# AltairLCD.net
KiCad netlist of a schematic drawn in EasyEDA
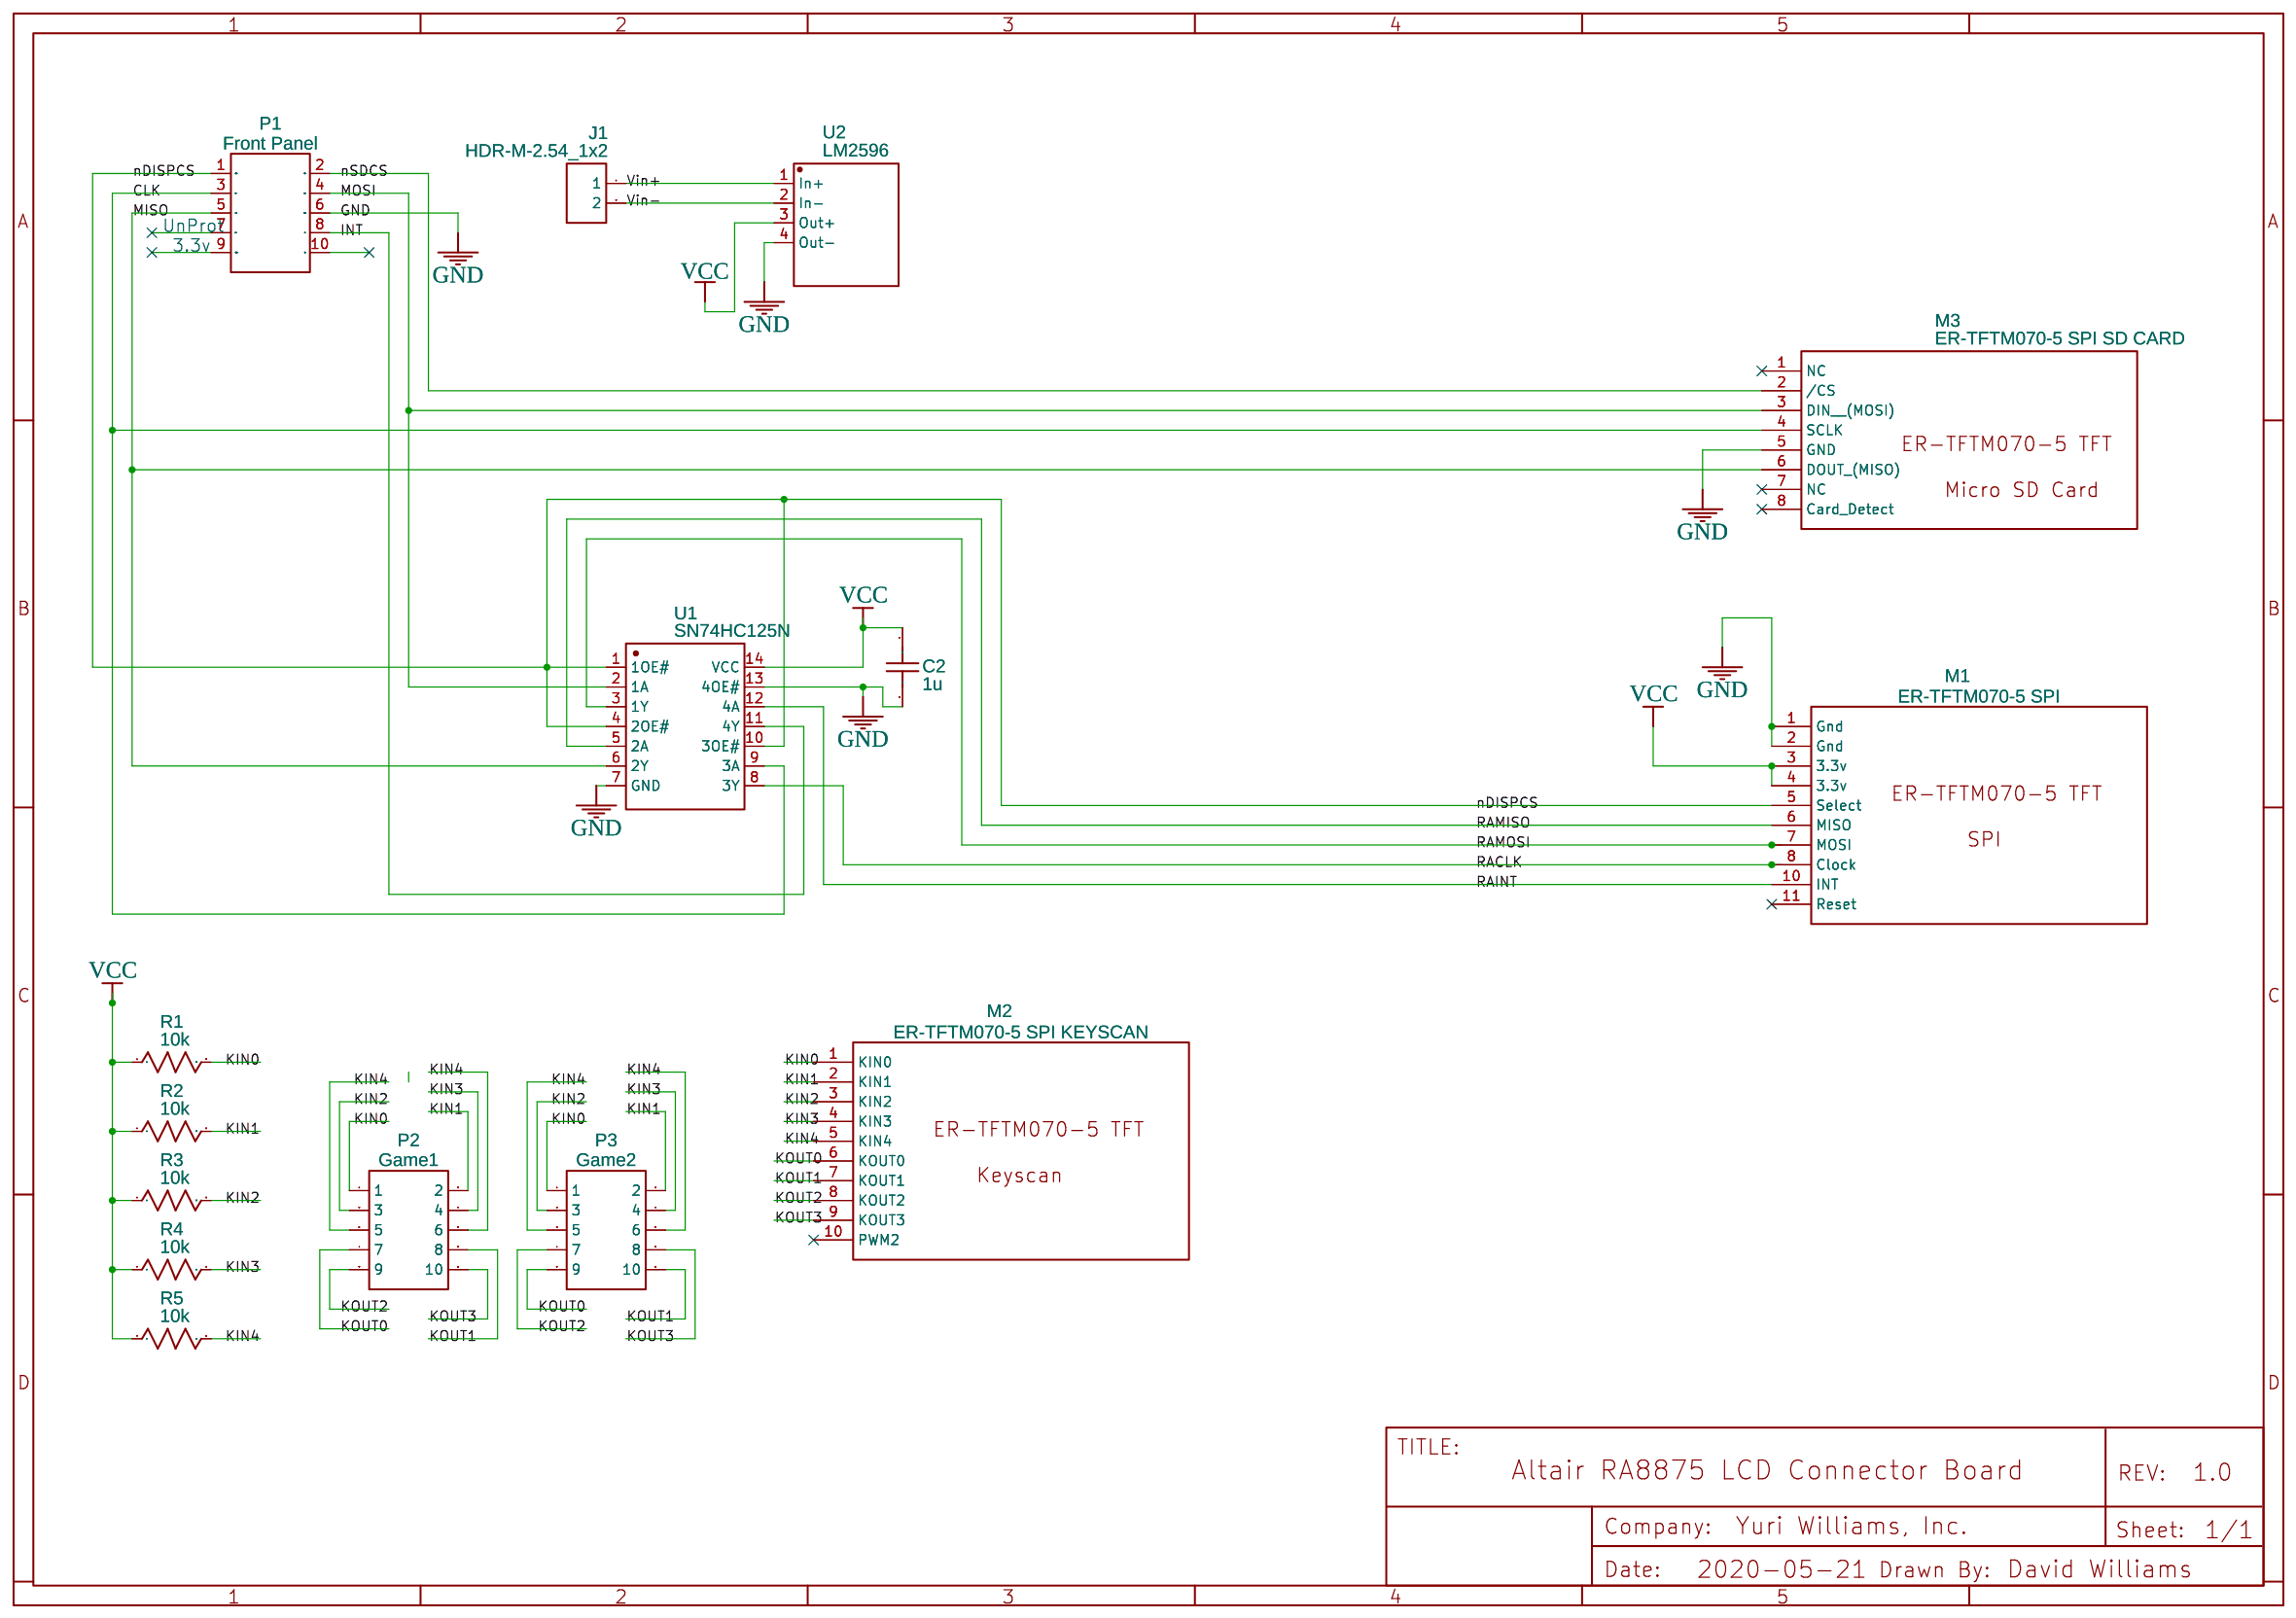
[diagram p0: schematic sheet]

(export (version "E")
  (design (tool "Eeschema 10.0.6"))
  (components
    (comp (ref "C2") (value "1u") (libsource (lib "") (part "C_RAD-0.1_US")))
    (comp (ref "J1")
      (value "HDR-M-2.54_1x2")
      (fields (field (name "BOM_Supplier Part") "C124375"))
      (libsource (lib "") (part "HDR-M-2.54_1x2"))
    )
    (comp (ref "M1")
      (value "ER-TFTM070-5 SPI")
      (fields
        (field (name "BOM_Manufacturer Part") "CD74HC125M")
        (field (name "BOM_Supplier Part") "ER-TFTM070-5")
      )
      (libsource (lib "") (part "ER-TFTM070-5 SPI"))
    )
    (comp (ref "M2")
      (value "ER-TFTM070-5 SPI KEYSCAN")
      (fields
        (field (name "BOM_Manufacturer Part") "CD74HC125M")
        (field (name "BOM_Supplier Part") "ER-TFTM070-5")
      )
      (libsource (lib "") (part "ER-TFTM070-5 SPI KEYSCAN"))
    )
    (comp (ref "M3")
      (value "ER-TFTM070-5 SPI SD CARD")
      (fields
        (field (name "BOM_Manufacturer Part") "CD74HC125M")
        (field (name "BOM_Supplier Part") "ER-TFTM070-5")
      )
      (libsource (lib "") (part "ER-TFTM070-5 SPI SD CARD"))
    )
    (comp (ref "P1")
      (value "Front Panel")
      (fields
        (field (name "BOM_Manufacturer Part") "IDC Box 2.54mm 2X5P")
        (field (name "BOM_Supplier Part") "C5665")
      )
      (libsource (lib "") (part "HDR-IDC-2.54-2X5P"))
    )
    (comp (ref "P2")
      (value "Game1")
      (fields
        (field (name "BOM_Manufacturer Part") "IDC Box 2.54mm 2X5P")
        (field (name "BOM_Supplier Part") "C5665")
      )
      (libsource (lib "") (part "HDR-IDC-2.54-2X5P_1"))
    )
    (comp (ref "P3")
      (value "Game2")
      (fields
        (field (name "BOM_Manufacturer Part") "IDC Box 2.54mm 2X5P")
        (field (name "BOM_Supplier Part") "C5665")
      )
      (libsource (lib "") (part "HDR-IDC-2.54-2X5P_1"))
    )
    (comp (ref "R1") (value "10k") (libsource (lib "") (part "R_AXIAL-0.3_US")))
    (comp (ref "R2") (value "10k") (libsource (lib "") (part "R_AXIAL-0.3_US")))
    (comp (ref "R3") (value "10k") (libsource (lib "") (part "R_AXIAL-0.3_US")))
    (comp (ref "R4") (value "10k") (libsource (lib "") (part "R_AXIAL-0.3_US")))
    (comp (ref "R5") (value "10k") (libsource (lib "") (part "R_AXIAL-0.3_US")))
    (comp (ref "U1")
      (value "SN74HC125N")
      (fields (field (name "BOM_Supplier Part") "C2890"))
      (libsource (lib "") (part "SN74HC125N"))
    )
    (comp (ref "U2") (value "LM2596") (libsource (lib "") (part "LM2596")))
  )
  (nets
    (net (code "1") (name "/CLK") (class "Default")
      (node (ref "M3") (pin "4") (pinfunction "SCLK_4") (pintype "unspecified"))
      (node (ref "P1") (pin "3") (pinfunction "CLK_3") (pintype "input"))
      (node (ref "U1") (pin "9") (pinfunction "3A_9") (pintype "unspecified"))
    )
    (net (code "2") (name "/INT") (class "Default")
      (node (ref "P1") (pin "8") (pinfunction "INT_8") (pintype "output"))
      (node (ref "U1") (pin "11") (pinfunction "4Y_11") (pintype "unspecified"))
    )
    (net (code "3") (name "/KIN0") (class "Default")
      (node (ref "M2") (pin "1") (pinfunction "KIN0_1") (pintype "unspecified"))
      (node (ref "P2") (pin "1") (pinfunction "1_1") (pintype "unspecified"))
      (node (ref "P3") (pin "1") (pinfunction "1_1") (pintype "unspecified"))
      (node (ref "R1") (pin "2") (pinfunction "2_2") (pintype "unspecified"))
    )
    (net (code "4") (name "/KIN1") (class "Default")
      (node (ref "M2") (pin "2") (pinfunction "KIN1_2") (pintype "unspecified"))
      (node (ref "P2") (pin "2") (pinfunction "2_2") (pintype "unspecified"))
      (node (ref "P3") (pin "2") (pinfunction "2_2") (pintype "unspecified"))
      (node (ref "R2") (pin "2") (pinfunction "2_2") (pintype "unspecified"))
    )
    (net (code "5") (name "/KIN2") (class "Default")
      (node (ref "M2") (pin "3") (pinfunction "KIN2_3") (pintype "unspecified"))
      (node (ref "P2") (pin "3") (pinfunction "3_3") (pintype "unspecified"))
      (node (ref "P3") (pin "3") (pinfunction "3_3") (pintype "unspecified"))
      (node (ref "R3") (pin "2") (pinfunction "2_2") (pintype "unspecified"))
    )
    (net (code "6") (name "/KIN3") (class "Default")
      (node (ref "M2") (pin "4") (pinfunction "KIN3_4") (pintype "unspecified"))
      (node (ref "P2") (pin "4") (pinfunction "4_4") (pintype "unspecified"))
      (node (ref "P3") (pin "4") (pinfunction "4_4") (pintype "unspecified"))
      (node (ref "R4") (pin "2") (pinfunction "2_2") (pintype "unspecified"))
    )
    (net (code "7") (name "/KIN4") (class "Default")
      (node (ref "M2") (pin "5") (pinfunction "KIN4_5") (pintype "unspecified"))
      (node (ref "P2") (pin "5") (pinfunction "5_5") (pintype "unspecified"))
      (node (ref "P2") (pin "6") (pinfunction "6_6") (pintype "unspecified"))
      (node (ref "P3") (pin "5") (pinfunction "5_5") (pintype "unspecified"))
      (node (ref "P3") (pin "6") (pinfunction "6_6") (pintype "unspecified"))
      (node (ref "R5") (pin "2") (pinfunction "2_2") (pintype "unspecified"))
    )
    (net (code "8") (name "/KOUT0") (class "Default")
      (node (ref "M2") (pin "6") (pinfunction "KOUT0_6") (pintype "unspecified"))
      (node (ref "P2") (pin "7") (pinfunction "7_7") (pintype "unspecified"))
      (node (ref "P3") (pin "9") (pinfunction "9_9") (pintype "unspecified"))
    )
    (net (code "9") (name "/KOUT1") (class "Default")
      (node (ref "M2") (pin "7") (pinfunction "KOUT1_7") (pintype "unspecified"))
      (node (ref "P2") (pin "8") (pinfunction "8_8") (pintype "unspecified"))
      (node (ref "P3") (pin "10") (pinfunction "10_10") (pintype "unspecified"))
    )
    (net (code "10") (name "/KOUT2") (class "Default")
      (node (ref "M2") (pin "8") (pinfunction "KOUT2_8") (pintype "unspecified"))
      (node (ref "P2") (pin "9") (pinfunction "9_9") (pintype "unspecified"))
      (node (ref "P3") (pin "7") (pinfunction "7_7") (pintype "unspecified"))
    )
    (net (code "11") (name "/KOUT3") (class "Default")
      (node (ref "M2") (pin "9") (pinfunction "KOUT3_9") (pintype "unspecified"))
      (node (ref "P2") (pin "10") (pinfunction "10_10") (pintype "unspecified"))
      (node (ref "P3") (pin "8") (pinfunction "8_8") (pintype "unspecified"))
    )
    (net (code "12") (name "/MISO") (class "Default")
      (node (ref "M3") (pin "6") (pinfunction "DOUT_(MISO)_6") (pintype "unspecified"))
      (node (ref "P1") (pin "5") (pinfunction "MISO_5") (pintype "output"))
      (node (ref "U1") (pin "6") (pinfunction "2Y_6") (pintype "unspecified"))
    )
    (net (code "13") (name "/MOSI") (class "Default")
      (node (ref "M3") (pin "3") (pinfunction "DIN__(MOSI)_3") (pintype "unspecified"))
      (node (ref "P1") (pin "4") (pinfunction "MOSI_4") (pintype "input"))
      (node (ref "U1") (pin "2") (pinfunction "1A_2") (pintype "unspecified"))
    )
    (net (code "14") (name "/RACLK") (class "Default")
      (node (ref "M1") (pin "8") (pinfunction "Clock_8") (pintype "unspecified"))
      (node (ref "U1") (pin "8") (pinfunction "3Y_8") (pintype "unspecified"))
    )
    (net (code "15") (name "/RAINT") (class "Default")
      (node (ref "M1") (pin "10") (pinfunction "INT_10") (pintype "unspecified"))
      (node (ref "U1") (pin "12") (pinfunction "4A_12") (pintype "unspecified"))
    )
    (net (code "16") (name "/RAMISO") (class "Default")
      (node (ref "M1") (pin "6") (pinfunction "MISO_6") (pintype "unspecified"))
      (node (ref "U1") (pin "5") (pinfunction "2A_5") (pintype "unspecified"))
    )
    (net (code "17") (name "/RAMOSI") (class "Default")
      (node (ref "M1") (pin "7") (pinfunction "MOSI_7") (pintype "unspecified"))
      (node (ref "U1") (pin "3") (pinfunction "1Y_3") (pintype "unspecified"))
    )
    (net (code "18") (name "/Vin+") (class "Default")
      (node (ref "J1") (pin "1") (pinfunction "1_1") (pintype "unspecified"))
      (node (ref "U2") (pin "1") (pinfunction "In+_1") (pintype "unspecified"))
    )
    (net (code "19") (name "/Vin-") (class "Default")
      (node (ref "J1") (pin "2") (pinfunction "2_2") (pintype "unspecified"))
      (node (ref "U2") (pin "2") (pinfunction "In-_2") (pintype "unspecified"))
    )
    (net (code "20") (name "/nDISPCS") (class "Default")
      (node (ref "M1") (pin "5") (pinfunction "Select_5") (pintype "unspecified"))
      (node (ref "P1") (pin "1") (pinfunction "nDISPCS_1") (pintype "input"))
      (node (ref "U1") (pin "1") (pinfunction "1OE#_1") (pintype "unspecified"))
      (node (ref "U1") (pin "10") (pinfunction "3OE#_10") (pintype "unspecified"))
      (node (ref "U1") (pin "4") (pinfunction "2OE#_4") (pintype "unspecified"))
    )
    (net (code "21") (name "/nSDCS") (class "Default")
      (node (ref "M3") (pin "2") (pinfunction "/CS_2") (pintype "unspecified"))
      (node (ref "P1") (pin "2") (pinfunction "GND_2") (pintype "unspecified"))
    )
    (net (code "22") (name "GND") (class "Default")
      (node (ref "C2") (pin "2") (pinfunction "2_2") (pintype "unspecified"))
      (node (ref "M1") (pin "1") (pinfunction "Gnd_1") (pintype "unspecified"))
      (node (ref "M1") (pin "2") (pinfunction "Gnd_2") (pintype "unspecified"))
      (node (ref "M3") (pin "5") (pinfunction "GND_5") (pintype "unspecified"))
      (node (ref "P1") (pin "6") (pinfunction "nSDCS_6") (pintype "input"))
      (node (ref "U1") (pin "13") (pinfunction "4OE#_13") (pintype "unspecified"))
      (node (ref "U1") (pin "7") (pinfunction "GND_7") (pintype "unspecified"))
      (node (ref "U2") (pin "4") (pinfunction "Out-_4") (pintype "unspecified"))
    )
    (net (code "23") (name "VCC") (class "Default")
      (node (ref "C2") (pin "1") (pinfunction "1_1") (pintype "unspecified"))
      (node (ref "M1") (pin "3") (pinfunction "3.3v_3") (pintype "unspecified"))
      (node (ref "M1") (pin "4") (pinfunction "3.3v_4") (pintype "unspecified"))
      (node (ref "R1") (pin "1") (pinfunction "1_1") (pintype "unspecified"))
      (node (ref "R2") (pin "1") (pinfunction "1_1") (pintype "unspecified"))
      (node (ref "R3") (pin "1") (pinfunction "1_1") (pintype "unspecified"))
      (node (ref "R4") (pin "1") (pinfunction "1_1") (pintype "unspecified"))
      (node (ref "R5") (pin "1") (pinfunction "1_1") (pintype "unspecified"))
      (node (ref "U1") (pin "14") (pinfunction "VCC_14") (pintype "unspecified"))
      (node (ref "U2") (pin "3") (pinfunction "Out+_3") (pintype "unspecified"))
    )
    (net (code "24") (name "unconnected-(M1-Reset-Pad11)") (class "Default")
      (node (ref "M1") (pin "11") (pinfunction "Reset_11") (pintype "unspecified+no_connect"))
    )
    (net (code "25") (name "unconnected-(M2-PWM2-Pad10)") (class "Default")
      (node (ref "M2") (pin "10") (pinfunction "PWM2_10") (pintype "unspecified+no_connect"))
    )
    (net (code "26") (name "unconnected-(M3-Card_Detect-Pad8)") (class "Default")
      (node (ref "M3") (pin "8") (pinfunction "Card_Detect_8") (pintype "unspecified+no_connect"))
    )
    (net (code "27") (name "unconnected-(M3-NC-Pad1)") (class "Default")
      (node (ref "M3") (pin "1") (pinfunction "NC_1") (pintype "unspecified+no_connect"))
    )
    (net (code "28") (name "unconnected-(M3-NC-Pad7)") (class "Default")
      (node (ref "M3") (pin "7") (pinfunction "NC_7") (pintype "unspecified+no_connect"))
    )
    (net (code "29") (name "unconnected-(P1-ALTAIR3.3v-Pad9)") (class "Default")
      (node (ref "P1") (pin "9") (pinfunction "ALTAIR3.3v_9") (pintype "passive+no_connect"))
    )
    (net (code "30") (name "unconnected-(P1-GP-Pad7)") (class "Default")
      (node (ref "P1") (pin "7") (pinfunction "GP_7") (pintype "bidirectional+no_connect"))
    )
    (net (code "31") (name "unconnected-(P1-NC-Pad10)") (class "Default")
      (node (ref "P1") (pin "10") (pinfunction "NC_10") (pintype "unspecified+no_connect"))
    )
  )
)
